# Inflarrojo.net
KiCad netlist of a schematic drawn in Altium Designer
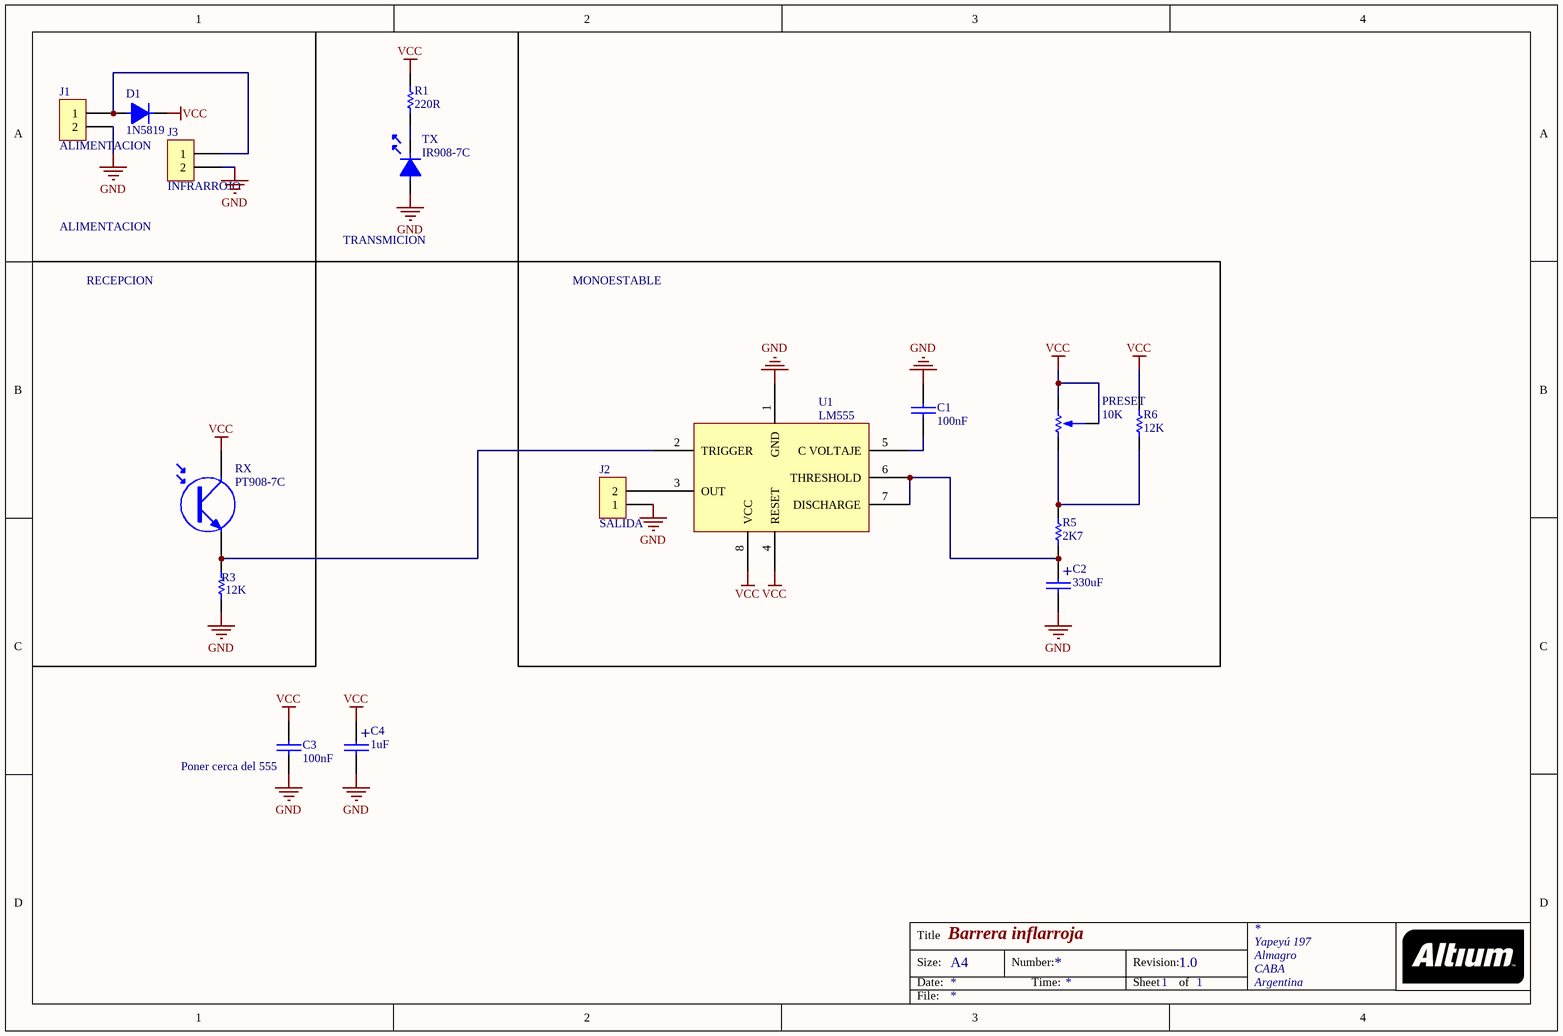
[diagram p0: Inflarrojo (2).SchDoc]

(export (version "E")
  (design (tool "Eeschema 10.0.6"))
  (components
    (comp (ref "C1") (value "100nF") (footprint "CAP200") (libsource (lib "LIBEBAL") (part "CAP")))
    (comp (ref "C2") (value "330uF") (footprint "CAP200RP") (libsource (lib "LIB-PIO-IX") (part "CAPPOL")))
    (comp (ref "C3") (value "100nF") (footprint "CAP200") (libsource (lib "LIBPIOIX 0314A") (part "CAP")))
    (comp (ref "C4") (value "1uF") (footprint "CAP100RP") (libsource (lib "LIBPIOIX 0314A") (part "CAPPOL")))
    (comp (ref "D1") (value "1N5819") (footprint "DO41") (libsource (lib "LIBPIOIX 0314A") (part "DIODO")))
    (comp (ref "J1") (value "ALIMENTACION") (footprint "BORNERA2") (libsource (lib "") (part "BORNERA 2_1")))
    (comp (ref "J2") (value "SALIDA") (footprint "BORNERA2") (libsource (lib "LIBPIOIX") (part "BORNERA 2")))
    (comp (ref "J3")
      (value "INFRARROJO")
      (footprint "BORNERA2")
      (libsource (lib "LIBEBAL") (part "BORNERA 2"))
    )
    (comp (ref "PRESET") (value "10K") (footprint "PRESET H") (libsource (lib "LIBEBAL") (part "PRESET")))
    (comp (ref "R1") (value "220R") (footprint "RES400") (libsource (lib "LIBEBAL") (part "RES")))
    (comp (ref "R3") (value "12K") (footprint "RES400") (libsource (lib "LIBEBAL") (part "RES")))
    (comp (ref "R5") (value "2K7") (footprint "RES400") (libsource (lib "LIBEBAL") (part "RES")))
    (comp (ref "R6") (value "12K") (footprint "RES400") (libsource (lib "LIBEBAL") (part "RES")))
    (comp (ref "RX")
      (value "PT908-7C")
      (footprint "pototransistor")
      (description "fototransistor")
      (libsource (lib "Libreria4") (part "PT908-7C"))
    )
    (comp (ref "TX")
      (value "IR908-7C")
      (footprint "fotodiodo")
      (description "Led infrarrojo")
      (libsource (lib "Libreria4") (part "IR908-7C"))
    )
    (comp (ref "U1")
      (value "LM555")
      (footprint "DIP8")
      (description "Timer")
      (libsource (lib "LIB-PIO-IX") (part "LM555"))
    )
  )
  (nets
    (net (code "1") (name "GND") (class "Default")
      (node (ref "C1") (pin "1") (pinfunction "1_1") (pintype "passive"))
      (node (ref "C2") (pin "2") (pinfunction "2_2") (pintype "passive"))
      (node (ref "C3") (pin "2") (pinfunction "2_2") (pintype "passive"))
      (node (ref "C4") (pin "2") (pinfunction "2_2") (pintype "passive"))
      (node (ref "J1") (pin "2") (pinfunction "2_2") (pintype "passive"))
      (node (ref "J2") (pin "1") (pinfunction "1_1") (pintype "passive"))
      (node (ref "J3") (pin "2") (pinfunction "2_2") (pintype "passive"))
      (node (ref "R3") (pin "1") (pinfunction "1_1") (pintype "passive"))
      (node (ref "TX") (pin "1") (pinfunction "1_1") (pintype "passive"))
      (node (ref "U1") (pin "1") (pinfunction "GND_1") (pintype "passive"))
    )
    (net (code "2") (name "Net-(D1-Pad1)") (class "Default")
      (node (ref "D1") (pin "1") (pinfunction "1_1") (pintype "passive"))
      (node (ref "J1") (pin "1") (pinfunction "1_1") (pintype "passive"))
      (node (ref "J3") (pin "1") (pinfunction "1_1") (pintype "passive"))
    )
    (net (code "3") (name "Net-(PRESET-Pad3)") (class "Default")
      (node (ref "PRESET") (pin "3") (pinfunction "3_3") (pintype "passive"))
      (node (ref "R5") (pin "2") (pinfunction "2_2") (pintype "passive"))
      (node (ref "R6") (pin "1") (pinfunction "1_1") (pintype "passive"))
    )
    (net (code "4") (name "Net-(R1-Pad1)") (class "Default")
      (node (ref "R1") (pin "1") (pinfunction "1_1") (pintype "passive"))
      (node (ref "TX") (pin "2") (pinfunction "2_2") (pintype "passive"))
    )
    (net (code "5") (name "Net-(RX-E)") (class "Default")
      (node (ref "R3") (pin "2") (pinfunction "2_2") (pintype "passive"))
      (node (ref "RX") (pin "1") (pinfunction "E_1") (pintype "passive"))
      (node (ref "U1") (pin "2") (pinfunction "TRIGGER_2") (pintype "passive"))
    )
    (net (code "6") (name "Net-(U1-C_VOLTAJE)") (class "Default")
      (node (ref "C1") (pin "2") (pinfunction "2_2") (pintype "passive"))
      (node (ref "U1") (pin "5") (pinfunction "C_VOLTAJE_5") (pintype "passive"))
    )
    (net (code "7") (name "Net-(U1-DISCHARGE)") (class "Default")
      (node (ref "C2") (pin "1") (pinfunction "1_1") (pintype "passive"))
      (node (ref "R5") (pin "1") (pinfunction "1_1") (pintype "passive"))
      (node (ref "U1") (pin "6") (pinfunction "THRESHOLD_6") (pintype "passive"))
      (node (ref "U1") (pin "7") (pinfunction "DISCHARGE_7") (pintype "passive"))
    )
    (net (code "8") (name "Net-(U1-OUT)") (class "Default")
      (node (ref "J2") (pin "2") (pinfunction "2_2") (pintype "passive"))
      (node (ref "U1") (pin "3") (pinfunction "OUT_3") (pintype "passive"))
    )
    (net (code "9") (name "VCC") (class "Default")
      (node (ref "C3") (pin "1") (pinfunction "1_1") (pintype "passive"))
      (node (ref "C4") (pin "1") (pinfunction "1_1") (pintype "passive"))
      (node (ref "D1") (pin "2") (pinfunction "2_2") (pintype "passive"))
      (node (ref "PRESET") (pin "1") (pinfunction "1_1") (pintype "passive"))
      (node (ref "PRESET") (pin "2") (pinfunction "2_2") (pintype "passive"))
      (node (ref "R1") (pin "2") (pinfunction "2_2") (pintype "passive"))
      (node (ref "R6") (pin "2") (pinfunction "2_2") (pintype "passive"))
      (node (ref "RX") (pin "2") (pinfunction "C_2") (pintype "passive"))
      (node (ref "U1") (pin "4") (pinfunction "RESET_4") (pintype "passive"))
      (node (ref "U1") (pin "8") (pinfunction "VCC_8") (pintype "passive"))
    )
  )
)
